# Power_Distribution_-_Power_Supply.net
KiCad netlist of a schematic drawn in Altium Designer
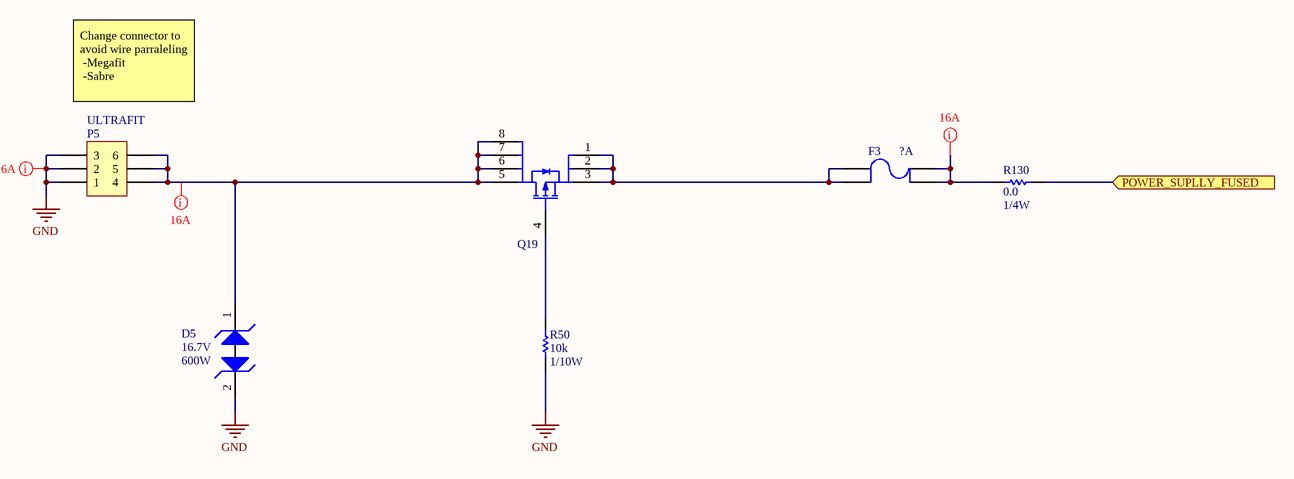
[diagram p0: Power Distribution - Power Supply.SchDoc]

(export (version "E")
  (design (tool "Eeschema 10.0.6"))
  (components
    (comp (ref "D5")
      (value "DIODE TVS 15VWM 24.4VC DO-214AA (SMB)")
      (footprint "DO-214AA Diode")
      (description "TVS DIODE 15VWM 24.4VC SMB")
      (fields (field (name "VOLTAGE - BREAKDOWN (MIN)") "16.7V") (field (name "POWER - PEAK PULSE") "600W"))
      (libsource (lib "Schematic Diagrams") (part "DIODE TVS 15VWM 24.4VC DO-214AA (SMB)"))
    )
    (comp (ref "F3")
      (value "?A")
      (footprint "FUSE ATO/ATC FUSE HOLDER")
      (description "Fuse Block 30A 500V 1 Circuit Blade PCB")
      (fields (field (name "VOLTAGE") "500V"))
      (libsource (lib "Schematic Diagrams") (part "FUSE ATO FUSE HOLDER"))
    )
    (comp (ref "P5")
      (value "CONN 6POS ULTRA-FIT 0.138\"")
      (footprint "CONN, 6POS ULTRA-FIT")
      (description "6 Positions Header Connector 0.138\" (3.50mm) Through Hole Tin")
      (fields (field (name "VOLTAGE") "400V") (field (name "SERIES") "ULTRAFIT"))
      (libsource (lib "Schematic Diagrams") (part "CONN 6POS ULTRA-FIT 0.138{dblquote}"))
    )
    (comp (ref "Q19")
      (value "MOSFET P-CH PWR56 40V 4.9 MOHM")
      (footprint "PMOS PWR56 40V 4.9 MOHM")
      (description "P-Channel 16V 2.5A (Ta) 650mW (Ta) Surface Mount X2-DFN2015-3")
      (libsource (lib "Schematic Diagrams") (part "MOSFET P-CH PWR56 40V 4.9 MOHM"))
    )
    (comp (ref "R50")
      (value "RES 10K OHM 1% 1/10W 0603")
      (footprint "RES, 0603")
      (description "RES SMD 10K OHM 1% 1/10W 0603")
      (fields
        (field (name "TOLERANCE") "±1%")
        (field (name "RESISTANCE") "10k")
        (field (name "POWER") "1/10W")
      )
      (libsource (lib "Schematic Diagrams") (part "RES 10K OHM 1% 1/10W 0603"))
    )
    (comp (ref "R130")
      (value "RES 0.0 OHM 1/4W 0603")
      (footprint "RES, 0603")
      (description "RES SMD 0.0 OHM JUMPER 1/4W 0603")
      (fields (field (name "RESISTANCE") "0.0") (field (name "POWER (WATTS)") "1/4W"))
      (libsource (lib "Schematic Diagrams") (part "RES 0.0 OHM 1/4W 0603"))
    )
  )
  (nets
    (net (code "1") (name "/POWER_SUPLLY_FUSED") (class "Default")
      (node (ref "R130") (pin "2") (pinfunction "2_2") (pintype "passive"))
    )
    (net (code "2") (name "GND") (class "Default")
      (node (ref "D5") (pin "2") (pinfunction "Cathode2_2") (pintype "passive"))
      (node (ref "P5") (pin "1") (pinfunction "1_1") (pintype "passive"))
      (node (ref "P5") (pin "2") (pinfunction "2_2") (pintype "passive"))
      (node (ref "P5") (pin "3") (pinfunction "3_3") (pintype "passive"))
      (node (ref "R50") (pin "2") (pinfunction "2_2") (pintype "passive"))
    )
    (net (code "3") (name "Net-(D5-Cathode1)") (class "Default")
      (node (ref "D5") (pin "1") (pinfunction "Cathode1_1") (pintype "passive"))
      (node (ref "P5") (pin "4") (pinfunction "4_4") (pintype "passive"))
      (node (ref "P5") (pin "5") (pinfunction "5_5") (pintype "passive"))
      (node (ref "P5") (pin "6") (pinfunction "6_6") (pintype "passive"))
      (node (ref "Q19") (pin "5") (pinfunction "D_5") (pintype "passive"))
      (node (ref "Q19") (pin "6") (pinfunction "D_6") (pintype "passive"))
      (node (ref "Q19") (pin "7") (pinfunction "D_7") (pintype "passive"))
      (node (ref "Q19") (pin "8") (pinfunction "D_8") (pintype "passive"))
    )
    (net (code "4") (name "Net-(F3-Pad1)") (class "Default")
      (node (ref "F3") (pin "1") (pinfunction "1_1") (pintype "passive"))
      (node (ref "F3") (pin "3") (pinfunction "3_3") (pintype "passive"))
      (node (ref "Q19") (pin "1") (pinfunction "S_1") (pintype "passive"))
      (node (ref "Q19") (pin "2") (pinfunction "S_2") (pintype "passive"))
      (node (ref "Q19") (pin "3") (pinfunction "S_3") (pintype "passive"))
    )
    (net (code "5") (name "Net-(F3-Pad2)") (class "Default")
      (node (ref "F3") (pin "2") (pinfunction "2_2") (pintype "passive"))
      (node (ref "F3") (pin "4") (pinfunction "4_4") (pintype "passive"))
      (node (ref "R130") (pin "1") (pinfunction "1_1") (pintype "passive"))
    )
    (net (code "6") (name "Net-(Q19-G)") (class "Default")
      (node (ref "Q19") (pin "4") (pinfunction "G_4") (pintype "passive"))
      (node (ref "R50") (pin "1") (pinfunction "1_1") (pintype "passive"))
    )
  )
)
